# 1_1-CameraExpansion.net
KiCad netlist of a schematic drawn in Altium Designer
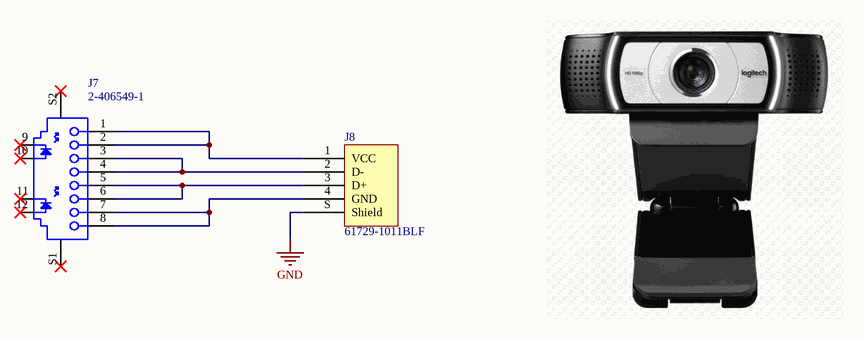
[diagram p0: 1_1-CameraExpansion.SchDoc]

(export (version "E")
  (design (tool "Eeschema 10.0.6"))
  (components
    (comp (ref "J7")
      (value "2-406549-1")
      (footprint "TECO-2-406549-1_V")
      (description "RJ45 Connector, Pitch 1.016 mm, 8 Position, Height 14.22 mm, Tail Length 3.18 mm, RoHS, Tray")
      (fields (field (name "MANUFACTURER") "TE Connectivity"))
      (libsource (lib "Altium Content Vault") (part "RJ45-12-2SHLD_A"))
    )
    (comp (ref "J8")
      (value "61729-1011BLF")
      (footprint "FCI USB 61729-1011BLF")
      (description "CONN RCPT USB2.0 TYPEB 4POS R/A")
      (fields
        (field (name "MANUFACTURER") "Amphenol ICC (FCI)")
        (field (name "LASTUPDATED") "9/12/2019 8:52:52 p. m.")
      )
      (libsource (lib "Celestial Altium Library - altium_library") (part "USB 2.0 Type B"))
    )
  )
  (nets
    (net (code "1") (name "GND") (class "Default")
      (node (ref "J8") (pin "S") (pinfunction "Shield_S") (pintype "passive"))
    )
    (net (code "2") (name "Net-(J8-D+)") (class "Default")
      (node (ref "J7") (pin "5") (pinfunction "5_5") (pintype "passive"))
      (node (ref "J7") (pin "6") (pinfunction "6_6") (pintype "passive"))
      (node (ref "J8") (pin "3") (pinfunction "D+_3") (pintype "passive"))
    )
    (net (code "3") (name "Net-(J8-D-)") (class "Default")
      (node (ref "J7") (pin "3") (pinfunction "3_3") (pintype "passive"))
      (node (ref "J7") (pin "4") (pinfunction "4_4") (pintype "passive"))
      (node (ref "J8") (pin "2") (pinfunction "D-_2") (pintype "passive"))
    )
    (net (code "4") (name "Net-(J8-GND)") (class "Default")
      (node (ref "J7") (pin "7") (pinfunction "7_7") (pintype "passive"))
      (node (ref "J7") (pin "8") (pinfunction "8_8") (pintype "passive"))
      (node (ref "J8") (pin "4") (pinfunction "GND_4") (pintype "passive"))
    )
    (net (code "5") (name "Net-(J8-VCC)") (class "Default")
      (node (ref "J7") (pin "1") (pinfunction "1_1") (pintype "passive"))
      (node (ref "J7") (pin "2") (pinfunction "2_2") (pintype "passive"))
      (node (ref "J8") (pin "1") (pinfunction "VCC_1") (pintype "passive"))
    )
    (net (code "6") (name "unconnected-(J7-Pad9)") (class "Default")
      (node (ref "J7") (pin "9") (pinfunction "9_9") (pintype "passive+no_connect"))
    )
    (net (code "7") (name "unconnected-(J7-Pad10)") (class "Default")
      (node (ref "J7") (pin "10") (pinfunction "10_10") (pintype "passive+no_connect"))
    )
    (net (code "8") (name "unconnected-(J7-Pad11)") (class "Default")
      (node (ref "J7") (pin "11") (pinfunction "11_11") (pintype "passive+no_connect"))
    )
    (net (code "9") (name "unconnected-(J7-Pad12)") (class "Default")
      (node (ref "J7") (pin "12") (pinfunction "12_12") (pintype "passive+no_connect"))
    )
    (net (code "10") (name "unconnected-(J7-PadS1)") (class "Default")
      (node (ref "J7") (pin "S1") (pinfunction "S1_S1") (pintype "passive+no_connect"))
    )
    (net (code "11") (name "unconnected-(J7-PadS2)") (class "Default")
      (node (ref "J7") (pin "S2") (pinfunction "S2_S2") (pintype "passive+no_connect"))
    )
  )
)
